# BNC-V002.net
KiCad netlist of a schematic drawn in EAGLE
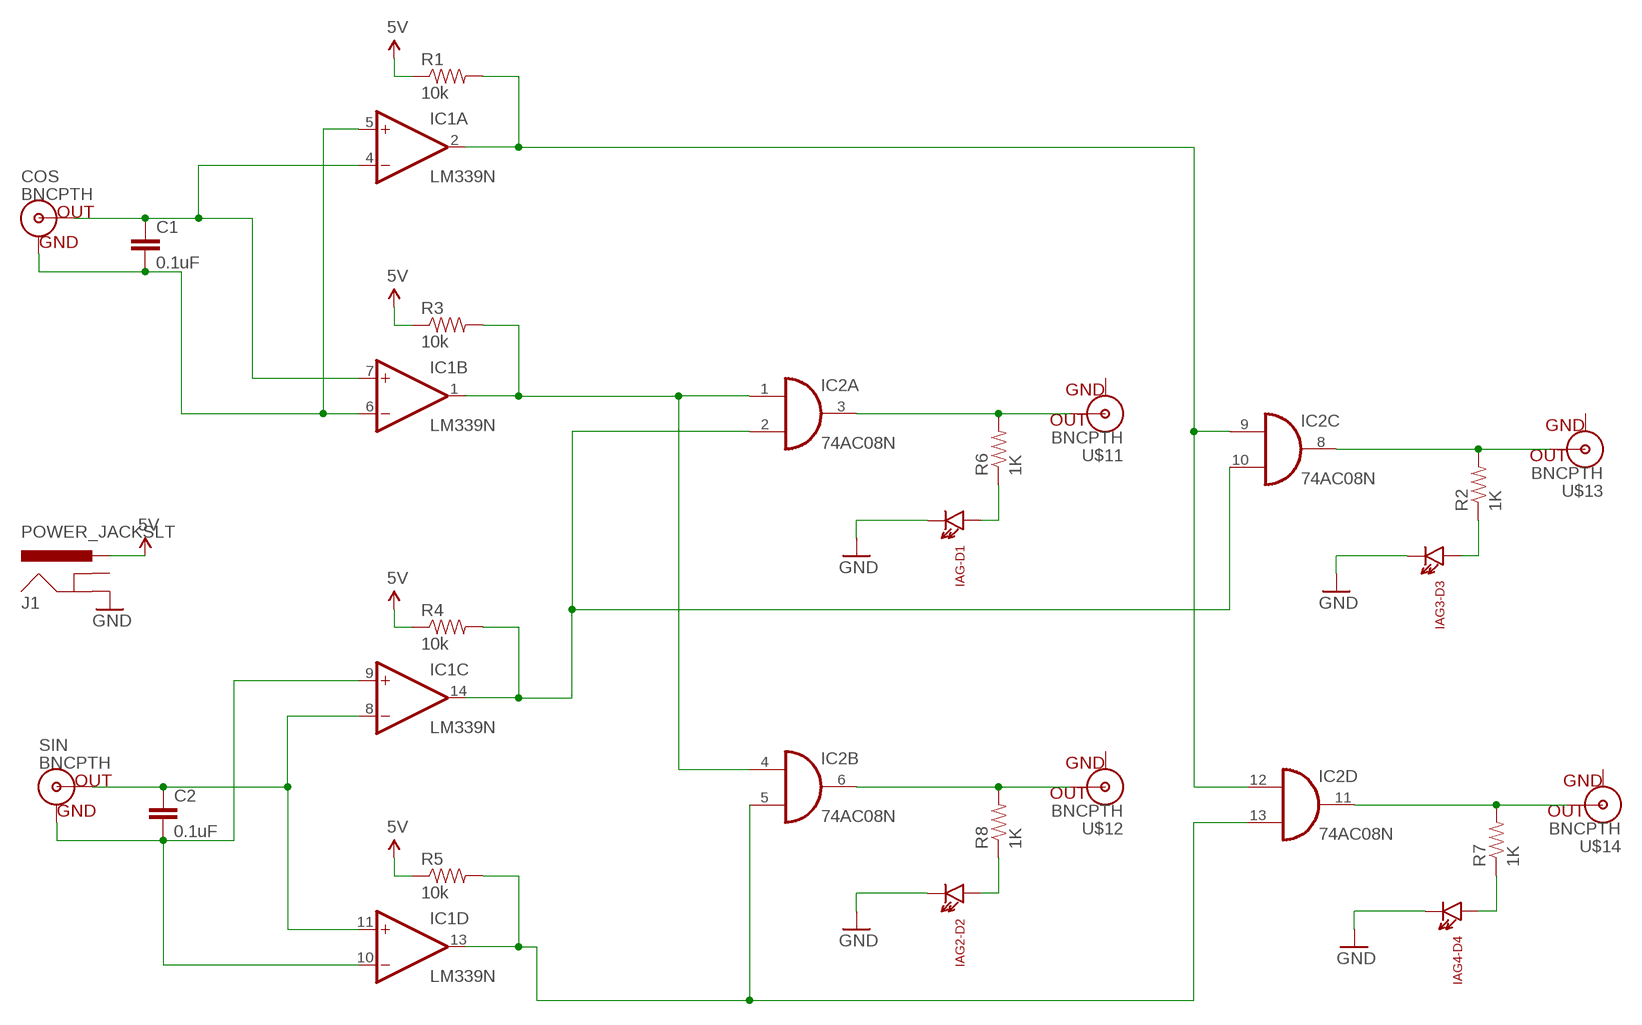
[diagram p0: schematic, sheet 1]

(export (version "E")
  (design (tool "Eeschema 10.0.6"))
  (components
    (comp (ref "C1")
      (value "0.1uF")
      (footprint "eagle-import:0603-CAP")
      (libsource (lib "eagle-import") (part "0.1UF-25V-5%(0603)"))
    )
    (comp (ref "C2")
      (value "0.1uF")
      (footprint "eagle-import:0603-CAP")
      (libsource (lib "eagle-import") (part "0.1UF-25V-5%(0603)"))
    )
    (comp (ref "COS")
      (value "BNCPTH")
      (footprint "eagle-import:BNC")
      (libsource (lib "eagle-import") (part "BNCPTH"))
    )
    (comp (ref "IAG-D1")
      (value "LTE-302")
      (footprint "eagle-import:LTE-302")
      (libsource (lib "eagle-import") (part "LTE-302"))
    )
    (comp (ref "IAG2-D2")
      (value "LTE-302")
      (footprint "eagle-import:LTE-302")
      (libsource (lib "eagle-import") (part "LTE-302"))
    )
    (comp (ref "IAG3-D3")
      (value "LTE-302")
      (footprint "eagle-import:LTE-302")
      (libsource (lib "eagle-import") (part "LTE-302"))
    )
    (comp (ref "IAG4-D4")
      (value "LTE-302")
      (footprint "eagle-import:LTE-302")
      (libsource (lib "eagle-import") (part "LTE-302"))
    )
    (comp (ref "IC1")
      (value "LM339N")
      (footprint "eagle-import:DIL14")
      (libsource (lib "eagle-import") (part "LM339N"))
    )
    (comp (ref "IC2")
      (value "74AC08N")
      (footprint "eagle-import:DIL14")
      (libsource (lib "eagle-import") (part "7408NAC"))
    )
    (comp (ref "J1")
      (value "POWER_JACKSLT")
      (footprint "eagle-import:POWER_JACK_SLOT")
      (libsource (lib "eagle-import") (part "POWER_JACKSLT"))
    )
    (comp (ref "R1")
      (value "10k")
      (footprint "eagle-import:AXIAL-0.3")
      (libsource (lib "eagle-import") (part "10KOHM-1/4W-1%(PTH)HORIZ"))
    )
    (comp (ref "R2")
      (value "1K")
      (footprint "eagle-import:AXIAL-0.3")
      (libsource (lib "eagle-import") (part "1KOHM-1/4W-1%(PTH)"))
    )
    (comp (ref "R3")
      (value "10k")
      (footprint "eagle-import:AXIAL-0.3")
      (libsource (lib "eagle-import") (part "10KOHM-1/4W-1%(PTH)HORIZ"))
    )
    (comp (ref "R4")
      (value "10k")
      (footprint "eagle-import:AXIAL-0.3")
      (libsource (lib "eagle-import") (part "10KOHM-1/4W-1%(PTH)HORIZ"))
    )
    (comp (ref "R5")
      (value "10k")
      (footprint "eagle-import:AXIAL-0.3")
      (libsource (lib "eagle-import") (part "10KOHM-1/4W-1%(PTH)HORIZ"))
    )
    (comp (ref "R6")
      (value "1K")
      (footprint "eagle-import:AXIAL-0.3")
      (libsource (lib "eagle-import") (part "1KOHM-1/4W-1%(PTH)"))
    )
    (comp (ref "R7")
      (value "1K")
      (footprint "eagle-import:AXIAL-0.3")
      (libsource (lib "eagle-import") (part "1KOHM-1/4W-1%(PTH)"))
    )
    (comp (ref "R8")
      (value "1K")
      (footprint "eagle-import:AXIAL-0.3")
      (libsource (lib "eagle-import") (part "1KOHM-1/4W-1%(PTH)"))
    )
    (comp (ref "SIN")
      (value "BNCPTH")
      (footprint "eagle-import:BNC")
      (libsource (lib "eagle-import") (part "BNCPTH"))
    )
    (comp (ref "U$11")
      (value "BNCPTH")
      (footprint "eagle-import:BNC")
      (libsource (lib "eagle-import") (part "BNCPTH"))
    )
    (comp (ref "U$12")
      (value "BNCPTH")
      (footprint "eagle-import:BNC")
      (libsource (lib "eagle-import") (part "BNCPTH"))
    )
    (comp (ref "U$13")
      (value "BNCPTH")
      (footprint "eagle-import:BNC")
      (libsource (lib "eagle-import") (part "BNCPTH"))
    )
    (comp (ref "U$14")
      (value "BNCPTH")
      (footprint "eagle-import:BNC")
      (libsource (lib "eagle-import") (part "BNCPTH"))
    )
  )
  (nets
    (net (code "1") (name "5V") (class "Default")
      (node (ref "J1") (pin "PWR") (pinfunction "PWR_PWR") (pintype "bidirectional"))
      (node (ref "R1") (pin "P$1") (pinfunction "1_P$1") (pintype "passive"))
      (node (ref "R3") (pin "P$1") (pinfunction "1_P$1") (pintype "passive"))
      (node (ref "R4") (pin "P$1") (pinfunction "1_P$1") (pintype "passive"))
      (node (ref "R5") (pin "P$1") (pinfunction "1_P$1") (pintype "passive"))
    )
    (net (code "2") (name "GND") (class "Default")
      (node (ref "IAG-D1") (pin "C") (pinfunction "C_C") (pintype "bidirectional"))
      (node (ref "IAG2-D2") (pin "C") (pinfunction "C_C") (pintype "bidirectional"))
      (node (ref "IAG3-D3") (pin "C") (pinfunction "C_C") (pintype "bidirectional"))
      (node (ref "IAG4-D4") (pin "C") (pinfunction "C_C") (pintype "bidirectional"))
      (node (ref "J1") (pin "GND@2") (pinfunction "GND_GND@2") (pintype "bidirectional"))
    )
    (net (code "3") (name "Net-(COS-OUT)") (class "Default")
      (node (ref "C1") (pin "1") (pinfunction "1_1") (pintype "passive"))
      (node (ref "COS") (pin "S") (pinfunction "OUT_S") (pintype "bidirectional"))
      (node (ref "IC1") (pin "4") (pinfunction "-IN_4") (pintype "input"))
      (node (ref "IC1") (pin "7") (pinfunction "+IN_7") (pintype "input"))
    )
    (net (code "4") (name "Net-(IC1A-+IN)") (class "Default")
      (node (ref "C1") (pin "2") (pinfunction "2_2") (pintype "passive"))
      (node (ref "COS") (pin "GND") (pinfunction "GND_GND") (pintype "bidirectional"))
      (node (ref "IC1") (pin "5") (pinfunction "+IN_5") (pintype "input"))
      (node (ref "IC1") (pin "6") (pinfunction "-IN_6") (pintype "input"))
    )
    (net (code "5") (name "Net-(IC1A-OUT)") (class "Default")
      (node (ref "IC1") (pin "2") (pinfunction "OUT_2") (pintype "open_collector"))
      (node (ref "IC2") (pin "12") (pinfunction "I0_12") (pintype "input"))
      (node (ref "IC2") (pin "9") (pinfunction "I0_9") (pintype "input"))
      (node (ref "R1") (pin "P$2") (pinfunction "2_P$2") (pintype "passive"))
    )
    (net (code "6") (name "Net-(IC1B-OUT)") (class "Default")
      (node (ref "IC1") (pin "1") (pinfunction "OUT_1") (pintype "open_collector"))
      (node (ref "IC2") (pin "1") (pinfunction "I0_1") (pintype "input"))
      (node (ref "IC2") (pin "4") (pinfunction "I0_4") (pintype "input"))
      (node (ref "R3") (pin "P$2") (pinfunction "2_P$2") (pintype "passive"))
    )
    (net (code "7") (name "Net-(IC1C-+IN)") (class "Default")
      (node (ref "C2") (pin "2") (pinfunction "2_2") (pintype "passive"))
      (node (ref "IC1") (pin "10") (pinfunction "-IN_10") (pintype "input"))
      (node (ref "IC1") (pin "9") (pinfunction "+IN_9") (pintype "input"))
      (node (ref "SIN") (pin "GND") (pinfunction "GND_GND") (pintype "bidirectional"))
    )
    (net (code "8") (name "Net-(IC1C--IN)") (class "Default")
      (node (ref "C2") (pin "1") (pinfunction "1_1") (pintype "passive"))
      (node (ref "IC1") (pin "11") (pinfunction "+IN_11") (pintype "input"))
      (node (ref "IC1") (pin "8") (pinfunction "-IN_8") (pintype "input"))
      (node (ref "SIN") (pin "S") (pinfunction "OUT_S") (pintype "bidirectional"))
    )
    (net (code "9") (name "Net-(IC1C-OUT)") (class "Default")
      (node (ref "IC1") (pin "14") (pinfunction "OUT_14") (pintype "open_collector"))
      (node (ref "IC2") (pin "10") (pinfunction "I1_10") (pintype "input"))
      (node (ref "IC2") (pin "2") (pinfunction "I1_2") (pintype "input"))
      (node (ref "R4") (pin "P$2") (pinfunction "2_P$2") (pintype "passive"))
    )
    (net (code "10") (name "Net-(IC1D-OUT)") (class "Default")
      (node (ref "IC1") (pin "13") (pinfunction "OUT_13") (pintype "open_collector"))
      (node (ref "IC2") (pin "13") (pinfunction "I1_13") (pintype "input"))
      (node (ref "IC2") (pin "5") (pinfunction "I1_5") (pintype "input"))
      (node (ref "R5") (pin "P$2") (pinfunction "2_P$2") (pintype "passive"))
    )
    (net (code "11") (name "Net-(IC2A-O)") (class "Default")
      (node (ref "IC2") (pin "3") (pinfunction "O_3") (pintype "output"))
      (node (ref "R6") (pin "P$2") (pinfunction "2_P$2") (pintype "passive"))
      (node (ref "U$11") (pin "S") (pinfunction "OUT_S") (pintype "bidirectional"))
    )
    (net (code "12") (name "Net-(IC2B-O)") (class "Default")
      (node (ref "IC2") (pin "6") (pinfunction "O_6") (pintype "output"))
      (node (ref "R8") (pin "P$2") (pinfunction "2_P$2") (pintype "passive"))
      (node (ref "U$12") (pin "S") (pinfunction "OUT_S") (pintype "bidirectional"))
    )
    (net (code "13") (name "Net-(IC2C-O)") (class "Default")
      (node (ref "IC2") (pin "8") (pinfunction "O_8") (pintype "output"))
      (node (ref "R2") (pin "P$2") (pinfunction "2_P$2") (pintype "passive"))
      (node (ref "U$13") (pin "S") (pinfunction "OUT_S") (pintype "bidirectional"))
    )
    (net (code "14") (name "Net-(IC2D-O)") (class "Default")
      (node (ref "IC2") (pin "11") (pinfunction "O_11") (pintype "output"))
      (node (ref "R7") (pin "P$2") (pinfunction "2_P$2") (pintype "passive"))
      (node (ref "U$14") (pin "S") (pinfunction "OUT_S") (pintype "bidirectional"))
    )
    (net (code "15") (name "Net-(R2-1)") (class "Default")
      (node (ref "IAG3-D3") (pin "A") (pinfunction "A_A") (pintype "bidirectional"))
      (node (ref "R2") (pin "P$1") (pinfunction "1_P$1") (pintype "passive"))
    )
    (net (code "16") (name "Net-(R6-1)") (class "Default")
      (node (ref "IAG-D1") (pin "A") (pinfunction "A_A") (pintype "bidirectional"))
      (node (ref "R6") (pin "P$1") (pinfunction "1_P$1") (pintype "passive"))
    )
    (net (code "17") (name "Net-(R7-1)") (class "Default")
      (node (ref "IAG4-D4") (pin "A") (pinfunction "A_A") (pintype "bidirectional"))
      (node (ref "R7") (pin "P$1") (pinfunction "1_P$1") (pintype "passive"))
    )
    (net (code "18") (name "Net-(R8-1)") (class "Default")
      (node (ref "IAG2-D2") (pin "A") (pinfunction "A_A") (pintype "bidirectional"))
      (node (ref "R8") (pin "P$1") (pinfunction "1_P$1") (pintype "passive"))
    )
    (net (code "19") (name "unconnected-(J1-GNDBREAK-PadGND@1)") (class "Default")
      (node (ref "J1") (pin "GND@1") (pinfunction "GNDBREAK_GND@1") (pintype "bidirectional"))
    )
    (net (code "20") (name "unconnected-(U$11-PadGND)") (class "Default")
      (node (ref "U$11") (pin "GND") (pinfunction "GND_GND") (pintype "bidirectional"))
    )
    (net (code "21") (name "unconnected-(U$12-PadGND)") (class "Default")
      (node (ref "U$12") (pin "GND") (pinfunction "GND_GND") (pintype "bidirectional"))
    )
    (net (code "22") (name "unconnected-(U$13-PadGND)") (class "Default")
      (node (ref "U$13") (pin "GND") (pinfunction "GND_GND") (pintype "bidirectional"))
    )
    (net (code "23") (name "unconnected-(U$14-PadGND)") (class "Default")
      (node (ref "U$14") (pin "GND") (pinfunction "GND_GND") (pintype "bidirectional"))
    )
  )
)
